# Coon85.net
KiCad netlist of a schematic drawn in EasyEDA
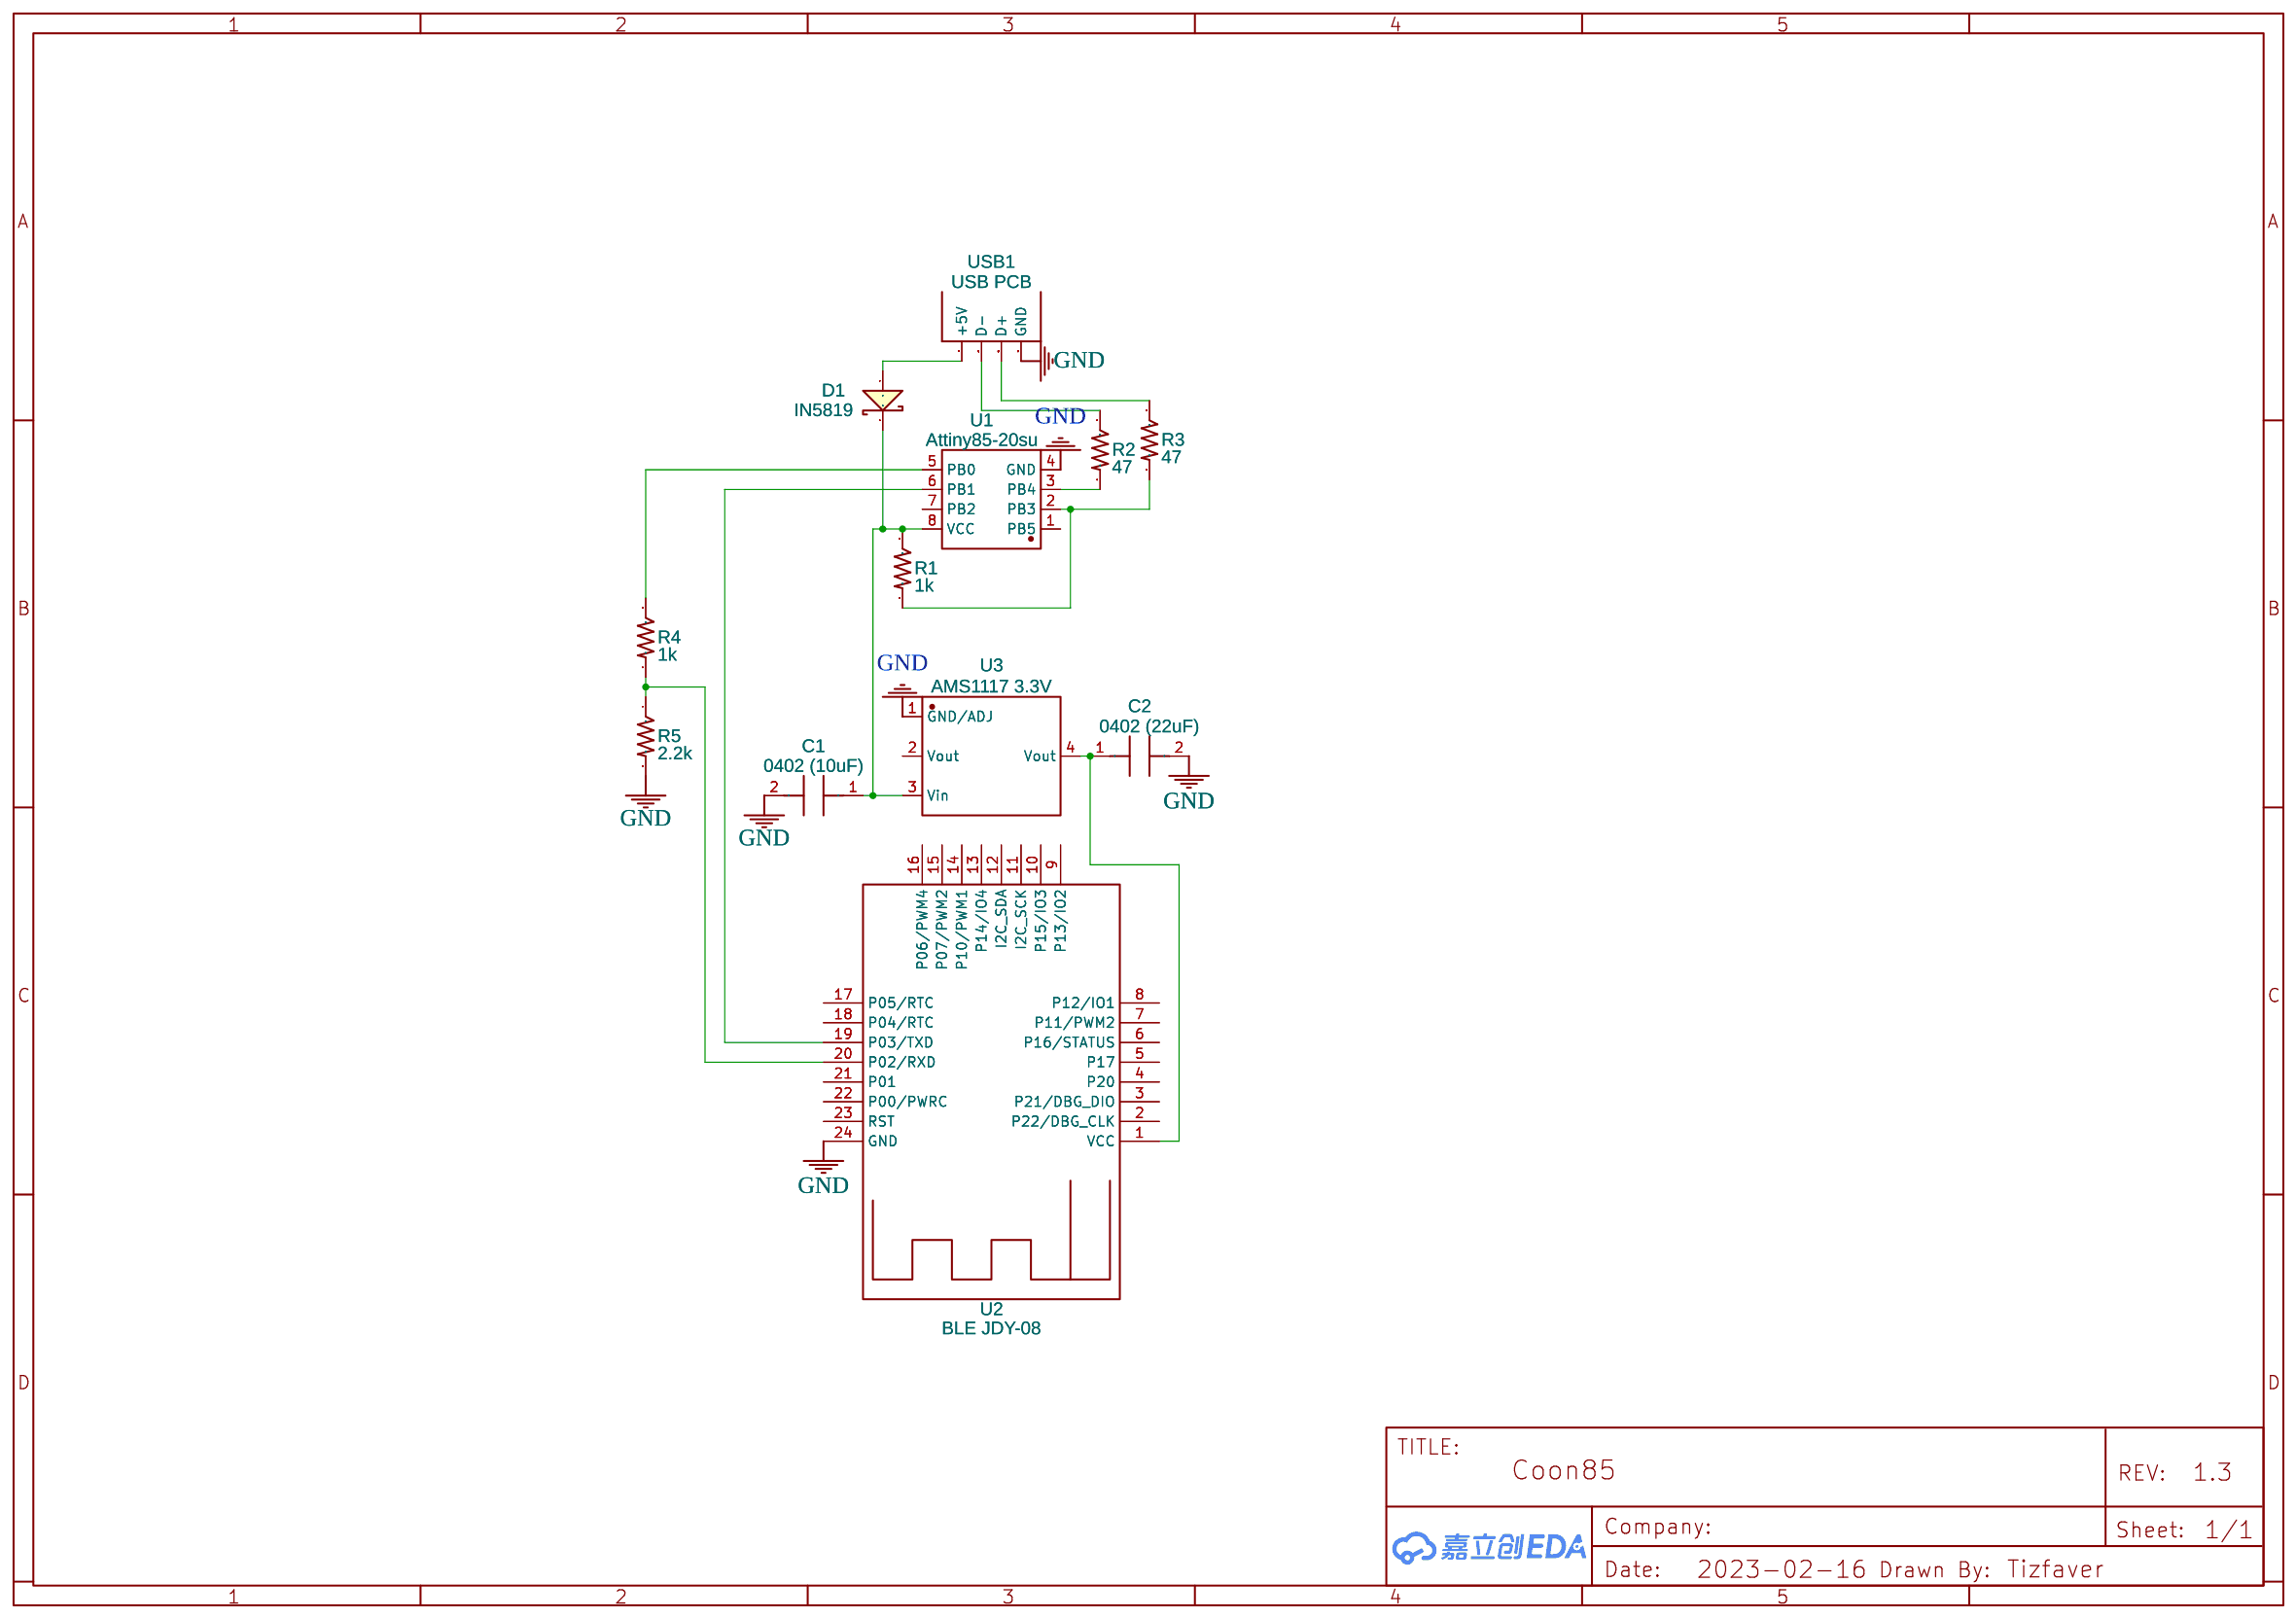
[diagram p0: schematic sheet]

(export (version "E")
  (design (tool "Eeschema 10.0.6"))
  (components
    (comp (ref "C1")
      (value "0402 (10uF)")
      (fields (field (name "BOM_Supplier Part") "712-1260-1-ND"))
      (libsource (lib "") (part "Capacitor (SMT) 0402 (0.1uF)"))
    )
    (comp (ref "C2")
      (value "0402 (22uF)")
      (fields (field (name "BOM_Supplier Part") "712-1260-1-ND"))
      (libsource (lib "") (part "Capacitor (SMT) 0402 (0.1uF)_1"))
    )
    (comp (ref "D1") (value "IN5819") (libsource (lib "") (part "IN5819")))
    (comp (ref "R1") (value "1k") (libsource (lib "") (part "SPARKFUN-RESISTORS_5.1KOHM-0402T-1/16W-1%")))
    (comp (ref "R2") (value "47") (libsource (lib "") (part "SPARKFUN-RESISTORS_5.1KOHM-0402T-1/16W-1%")))
    (comp (ref "R3") (value "47") (libsource (lib "") (part "SPARKFUN-RESISTORS_5.1KOHM-0402T-1/16W-1%")))
    (comp (ref "R4") (value "1k") (libsource (lib "") (part "SPARKFUN-RESISTORS_5.1KOHM-0402T-1/16W-1%")))
    (comp (ref "R5") (value "2.2k") (libsource (lib "") (part "SPARKFUN-RESISTORS_5.1KOHM-0402T-1/16W-1%")))
    (comp (ref "U1") (value "Attiny85-20su") (libsource (lib "") (part "Attiny85_01")))
    (comp (ref "U2")
      (value "BLE JDY-08")
      (fields (field (name "BOM_Manufacturer Part") "JDY-08"))
      (libsource (lib "") (part "BLE JDY-08"))
    )
    (comp (ref "U3")
      (value "AMS1117 3.3V")
      (fields (field (name "BOM_Manufacturer Part") "AMS1117-3.3") (field (name "BOM_Supplier Part") "C6186"))
      (libsource (lib "") (part "AMS1117 3.3V"))
    )
    (comp (ref "USB1") (value "USB PCB") (libsource (lib "") (part "USB PCB")))
  )
  (nets
    (net (code "1") (name "GND") (class "Default")
      (node (ref "C1") (pin "2") (pinfunction "2_2") (pintype "unspecified"))
      (node (ref "C2") (pin "2") (pinfunction "2_2") (pintype "unspecified"))
      (node (ref "R5") (pin "2") (pinfunction "2_2") (pintype "bidirectional"))
      (node (ref "U1") (pin "4") (pinfunction "GND_4") (pintype "unspecified"))
      (node (ref "U2") (pin "24") (pinfunction "GND_24") (pintype "unspecified"))
      (node (ref "U3") (pin "1") (pinfunction "GND/ADJ_1") (pintype "unspecified"))
      (node (ref "USB1") (pin "GND") (pinfunction "GND_GND") (pintype "unspecified"))
    )
    (net (code "2") (name "Net-(U1-PB0)") (class "Default")
      (node (ref "R4") (pin "1") (pinfunction "1_1") (pintype "bidirectional"))
      (node (ref "U1") (pin "5") (pinfunction "PB0_5") (pintype "unspecified"))
    )
    (net (code "3") (name "Net-(U1-PB1)") (class "Default")
      (node (ref "U1") (pin "6") (pinfunction "PB1_6") (pintype "unspecified"))
      (node (ref "U2") (pin "19") (pinfunction "P03/TXD_19") (pintype "unspecified"))
    )
    (net (code "4") (name "Net-(U1-PB3)") (class "Default")
      (node (ref "R1") (pin "2") (pinfunction "2_2") (pintype "bidirectional"))
      (node (ref "R3") (pin "2") (pinfunction "2_2") (pintype "bidirectional"))
      (node (ref "U1") (pin "2") (pinfunction "PB3_2") (pintype "unspecified"))
    )
    (net (code "5") (name "Net-(U1-PB4)") (class "Default")
      (node (ref "R2") (pin "2") (pinfunction "2_2") (pintype "bidirectional"))
      (node (ref "U1") (pin "3") (pinfunction "PB4_3") (pintype "unspecified"))
    )
    (net (code "6") (name "Net-(U1-VCC)") (class "Default")
      (node (ref "C1") (pin "1") (pinfunction "1_1") (pintype "unspecified"))
      (node (ref "D1") (pin "2") (pinfunction "2_2") (pintype "unspecified"))
      (node (ref "R1") (pin "1") (pinfunction "1_1") (pintype "bidirectional"))
      (node (ref "U1") (pin "8") (pinfunction "VCC_8") (pintype "unspecified"))
      (node (ref "U3") (pin "3") (pinfunction "Vin_3") (pintype "unspecified"))
    )
    (net (code "7") (name "Net-(U2-P02{slash}RXD)") (class "Default")
      (node (ref "R4") (pin "2") (pinfunction "2_2") (pintype "bidirectional"))
      (node (ref "R5") (pin "1") (pinfunction "1_1") (pintype "bidirectional"))
      (node (ref "U2") (pin "20") (pinfunction "P02/RXD_20") (pintype "unspecified"))
    )
    (net (code "8") (name "Net-(U2-VCC)") (class "Default")
      (node (ref "C2") (pin "1") (pinfunction "1_1") (pintype "unspecified"))
      (node (ref "U2") (pin "1") (pinfunction "VCC_1") (pintype "unspecified"))
      (node (ref "U3") (pin "4") (pinfunction "Vout_4") (pintype "unspecified"))
    )
    (net (code "9") (name "Net-(USB1-+5V)") (class "Default")
      (node (ref "D1") (pin "1") (pinfunction "1_1") (pintype "unspecified"))
      (node (ref "USB1") (pin "5V") (pinfunction "+5V_5V") (pintype "unspecified"))
    )
    (net (code "10") (name "Net-(USB1-D+)") (class "Default")
      (node (ref "R3") (pin "1") (pinfunction "1_1") (pintype "bidirectional"))
      (node (ref "USB1") (pin "USB_P") (pinfunction "D+_USB_P") (pintype "unspecified"))
    )
    (net (code "11") (name "Net-(USB1-D-)") (class "Default")
      (node (ref "R2") (pin "1") (pinfunction "1_1") (pintype "bidirectional"))
      (node (ref "USB1") (pin "USB_M") (pinfunction "D-_USB_M") (pintype "unspecified"))
    )
    (net (code "12") (name "unconnected-(U1-PB2-Pad7)") (class "Default")
      (node (ref "U1") (pin "7") (pinfunction "PB2_7") (pintype "unspecified"))
    )
    (net (code "13") (name "unconnected-(U1-PB5-Pad1)") (class "Default")
      (node (ref "U1") (pin "1") (pinfunction "PB5_1") (pintype "unspecified"))
    )
    (net (code "14") (name "unconnected-(U2-I2C_SCK-Pad11)") (class "Default")
      (node (ref "U2") (pin "11") (pinfunction "I2C_SCK_11") (pintype "unspecified"))
    )
    (net (code "15") (name "unconnected-(U2-I2C_SDA-Pad12)") (class "Default")
      (node (ref "U2") (pin "12") (pinfunction "I2C_SDA_12") (pintype "unspecified"))
    )
    (net (code "16") (name "unconnected-(U2-P00{slash}PWRC-Pad22)") (class "Default")
      (node (ref "U2") (pin "22") (pinfunction "P00/PWRC_22") (pintype "unspecified"))
    )
    (net (code "17") (name "unconnected-(U2-P01-Pad21)") (class "Default")
      (node (ref "U2") (pin "21") (pinfunction "P01_21") (pintype "unspecified"))
    )
    (net (code "18") (name "unconnected-(U2-P04{slash}RTC-Pad18)") (class "Default")
      (node (ref "U2") (pin "18") (pinfunction "P04/RTC_18") (pintype "unspecified"))
    )
    (net (code "19") (name "unconnected-(U2-P05{slash}RTC-Pad17)") (class "Default")
      (node (ref "U2") (pin "17") (pinfunction "P05/RTC_17") (pintype "unspecified"))
    )
    (net (code "20") (name "unconnected-(U2-P06{slash}PWM4-Pad16)") (class "Default")
      (node (ref "U2") (pin "16") (pinfunction "P06/PWM4_16") (pintype "unspecified"))
    )
    (net (code "21") (name "unconnected-(U2-P07{slash}PWM2-Pad15)") (class "Default")
      (node (ref "U2") (pin "15") (pinfunction "P07/PWM2_15") (pintype "unspecified"))
    )
    (net (code "22") (name "unconnected-(U2-P10{slash}PWM1-Pad14)") (class "Default")
      (node (ref "U2") (pin "14") (pinfunction "P10/PWM1_14") (pintype "unspecified"))
    )
    (net (code "23") (name "unconnected-(U2-P11{slash}PWM2-Pad7)") (class "Default")
      (node (ref "U2") (pin "7") (pinfunction "P11/PWM2_7") (pintype "unspecified"))
    )
    (net (code "24") (name "unconnected-(U2-P12{slash}IO1-Pad8)") (class "Default")
      (node (ref "U2") (pin "8") (pinfunction "P12/IO1_8") (pintype "unspecified"))
    )
    (net (code "25") (name "unconnected-(U2-P13{slash}IO2-Pad9)") (class "Default")
      (node (ref "U2") (pin "9") (pinfunction "P13/IO2_9") (pintype "unspecified"))
    )
    (net (code "26") (name "unconnected-(U2-P14{slash}IO4-Pad13)") (class "Default")
      (node (ref "U2") (pin "13") (pinfunction "P14/IO4_13") (pintype "unspecified"))
    )
    (net (code "27") (name "unconnected-(U2-P15{slash}IO3-Pad10)") (class "Default")
      (node (ref "U2") (pin "10") (pinfunction "P15/IO3_10") (pintype "unspecified"))
    )
    (net (code "28") (name "unconnected-(U2-P16{slash}STATUS-Pad6)") (class "Default")
      (node (ref "U2") (pin "6") (pinfunction "P16/STATUS_6") (pintype "unspecified"))
    )
    (net (code "29") (name "unconnected-(U2-P17-Pad5)") (class "Default")
      (node (ref "U2") (pin "5") (pinfunction "P17_5") (pintype "unspecified"))
    )
    (net (code "30") (name "unconnected-(U2-P20-Pad4)") (class "Default")
      (node (ref "U2") (pin "4") (pinfunction "P20_4") (pintype "unspecified"))
    )
    (net (code "31") (name "unconnected-(U2-P21{slash}DBG_DIO-Pad3)") (class "Default")
      (node (ref "U2") (pin "3") (pinfunction "P21/DBG_DIO_3") (pintype "unspecified"))
    )
    (net (code "32") (name "unconnected-(U2-P22{slash}DBG_CLK-Pad2)") (class "Default")
      (node (ref "U2") (pin "2") (pinfunction "P22/DBG_CLK_2") (pintype "unspecified"))
    )
    (net (code "33") (name "unconnected-(U2-RST-Pad23)") (class "Default")
      (node (ref "U2") (pin "23") (pinfunction "RST_23") (pintype "unspecified"))
    )
    (net (code "34") (name "unconnected-(U3-Vout-Pad2)") (class "Default")
      (node (ref "U3") (pin "2") (pinfunction "Vout_2") (pintype "unspecified"))
    )
  )
)
